# 18-GSM_GPRS_SIM808.net
KiCad netlist of a schematic drawn in Altium Designer
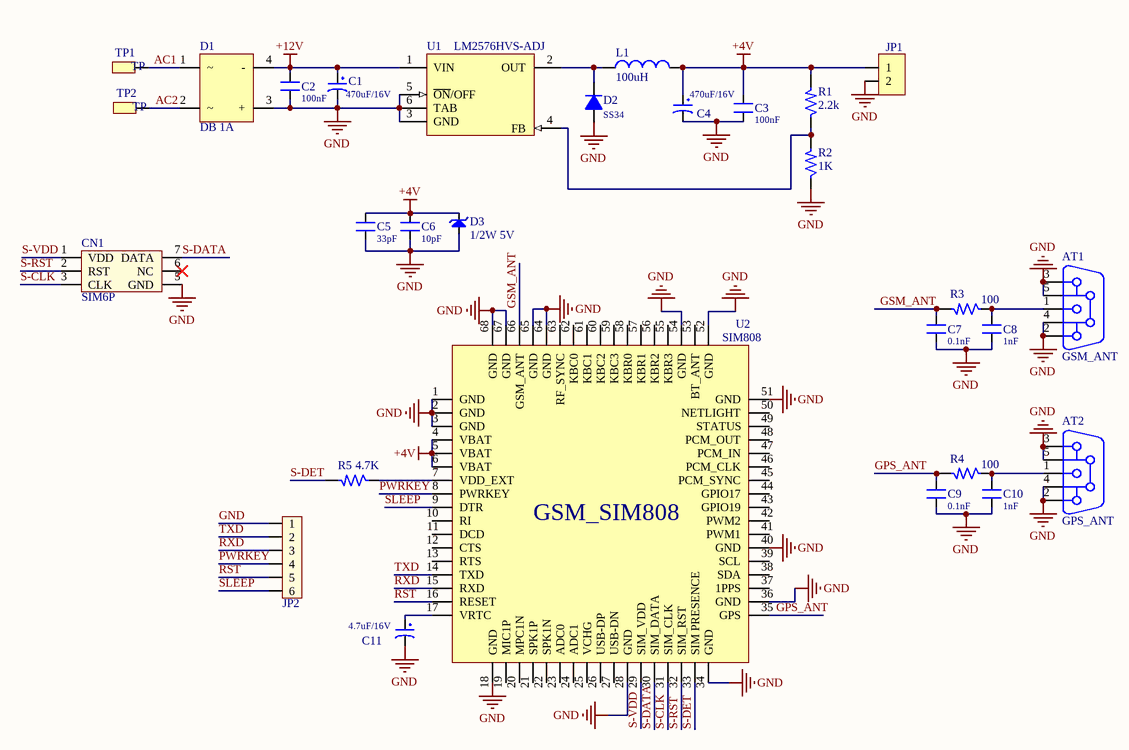
[diagram p0: 18-GSM_GPRS (SIM808).SchDoc]

(export (version "E")
  (design (tool "Eeschema 10.0.6"))
  (components
    (comp (ref "AT1")
      (value "GSM_ANT")
      (footprint "SMA-RA")
      (description "CONNECTOR ANTEN")
      (fields
        (field (name "PARTNO") "210111003")
        (field (name "MANUFACTURER") "Würth Elektronik eiSos GmbH")
        (field (name "CREATED BY") "Christin Zierenner")
      )
      (libsource (lib "LIBRARY") (part "CON Ant"))
    )
    (comp (ref "AT2")
      (value "GPS_ANT")
      (footprint "SMA-RA")
      (description "CONNECTOR ANTEN")
      (fields
        (field (name "PARTNO") "210111003")
        (field (name "MANUFACTURER") "Würth Elektronik eiSos GmbH")
        (field (name "CREATED BY") "Christin Zierenner")
      )
      (libsource (lib "LIBRARY") (part "CON Ant"))
    )
    (comp (ref "C1")
      (value "470uF/16V")
      (footprint "C-TANT-7343")
      (libsource (lib "MrQuan") (part "Capacitor"))
    )
    (comp (ref "C2") (value "100nF") (footprint "CER-0805") (libsource (lib "MrQuan") (part "Ceramic")))
    (comp (ref "C3") (value "100nF") (footprint "CER-0805") (libsource (lib "MrQuan") (part "Ceramic")))
    (comp (ref "C4")
      (value "470uF/16V")
      (footprint "C-TANT-7343")
      (libsource (lib "MrQuan") (part "Capacitor"))
    )
    (comp (ref "C5") (value "33pF") (footprint "CER-0805") (libsource (lib "MrQuan") (part "Ceramic")))
    (comp (ref "C6") (value "10pF") (footprint "CER-0805") (libsource (lib "MrQuan") (part "Ceramic")))
    (comp (ref "C7") (value "0.1nF") (footprint "CER-0805") (libsource (lib "MrQuan") (part "Ceramic")))
    (comp (ref "C8") (value "1nF") (footprint "CER-0805") (libsource (lib "MrQuan") (part "Ceramic")))
    (comp (ref "C9") (value "0.1nF") (footprint "CER-0805") (libsource (lib "MrQuan") (part "Ceramic")))
    (comp (ref "C10") (value "1nF") (footprint "CER-0805") (libsource (lib "MrQuan") (part "Ceramic")))
    (comp (ref "C11")
      (value "4.7uF/16V")
      (footprint "C-TANT-7343")
      (libsource (lib "MrQuan") (part "Capacitor"))
    )
    (comp (ref "CN1")
      (value "SIM6P")
      (footprint "SK-SIM-C707A")
      (libsource (lib "doAnTotNghiep2017Lib") (part "SIM6P"))
    )
    (comp (ref "D1")
      (value "DB 1A")
      (footprint "D-DB-1A-SMD")
      (libsource (lib "doAnTotNghiep2017Lib") (part "DB"))
    )
    (comp (ref "D2") (value "SS34") (footprint "DO-214AC") (libsource (lib "MrQuan") (part "Diode")))
    (comp (ref "D3")
      (value "1/2W 5V")
      (footprint "DIO-SMD-106")
      (description "Zenner")
      (libsource (lib "LIBRARY") (part "DIODE Zener"))
    )
    (comp (ref "JP1")
      (value "JP2")
      (footprint "JP2-C1T")
      (description "WR-PHD 2.54 mm Angled Socket Header")
      (fields
        (field (name "MANUFACTURER") "Würth Elektronik eiSos GmbH")
        (field (name "PARTNO") "613002143121")
        (field (name "CREATED BY") "Karrer Zheng")
      )
      (libsource (lib "LIBRARY") (part "JP2"))
    )
    (comp (ref "JP2") (value "JP6 PIN") (footprint "JP6") (libsource (lib "syhaunguyen") (part "JP6")))
    (comp (ref "L1")
      (value "100uH")
      (footprint "SMD-L-X10-Y10-Z4")
      (description "Inductor")
      (fields (field (name "PUBLISHER") "Altium Limited"))
      (libsource (lib "VNSKILLS2014-ASM") (part "Inductor"))
    )
    (comp (ref "R1") (value "2.2k") (footprint "RES-0805") (libsource (lib "MrQuan") (part "Res1/4W")))
    (comp (ref "R2") (value "1K") (footprint "RES-0805") (libsource (lib "MrQuan") (part "Res1/4W")))
    (comp (ref "R3") (value "100") (footprint "RES-0805") (libsource (lib "MrQuan") (part "Res1/4W")))
    (comp (ref "R4") (value "100") (footprint "RES-0805") (libsource (lib "MrQuan") (part "Res1/4W")))
    (comp (ref "R5") (value "4.7K") (footprint "RES-0805") (libsource (lib "MrQuan") (part "Res1/4W")))
    (comp (ref "TP1")
      (value "1")
      (footprint "TP")
      (description "CONNECT 1")
      (libsource (lib "PART") (part "TP"))
    )
    (comp (ref "TP2")
      (value "1")
      (footprint "TP")
      (description "CONNECT 1")
      (libsource (lib "PART") (part "TP"))
    )
    (comp (ref "U1")
      (value "LM2576HVS-ADJ")
      (footprint "LM2576")
      (description "SIMPLE SWITCHER; 3A Step-Down Voltage Regulator")
      (fields
        (field (name "PARTNUMBER") "LM2576HVS-5.0")
        (field (name "MANUFACTURER") "National Semiconductor")
        (field (name "PUBLISHER") "Altium Limited")
      )
      (libsource (lib "VNSKILLS2014-ASM") (part "LM2576HVS-5.0"))
    )
    (comp (ref "U2") (value "SIM808") (footprint "GSM-SIM808") (libsource (lib "MrQuan") (part "GSM-Sim808")))
  )
  (nets
    (net (code "1") (name "+4V") (class "Default")
      (node (ref "C3") (pin "2") (pinfunction "2_2") (pintype "passive"))
      (node (ref "C4") (pin "1") (pinfunction "1_1") (pintype "passive"))
      (node (ref "C5") (pin "2") (pinfunction "2_2") (pintype "passive"))
      (node (ref "C6") (pin "2") (pinfunction "2_2") (pintype "passive"))
      (node (ref "D3") (pin "2") (pinfunction "K_2") (pintype "passive"))
      (node (ref "JP1") (pin "1") (pinfunction "1_1") (pintype "passive"))
      (node (ref "L1") (pin "2") (pinfunction "2_2") (pintype "passive"))
      (node (ref "R1") (pin "2") (pinfunction "2_2") (pintype "passive"))
      (node (ref "U2") (pin "4") (pinfunction "VBAT_4") (pintype "passive"))
      (node (ref "U2") (pin "5") (pinfunction "VBAT_5") (pintype "passive"))
      (node (ref "U2") (pin "6") (pinfunction "VBAT_6") (pintype "passive"))
    )
    (net (code "2") (name "+12V") (class "Default")
      (node (ref "C1") (pin "1") (pinfunction "1_1") (pintype "passive"))
      (node (ref "C2") (pin "2") (pinfunction "2_2") (pintype "passive"))
      (node (ref "D1") (pin "4") (pinfunction "-_4") (pintype "passive"))
      (node (ref "U1") (pin "1") (pinfunction "VIN_1") (pintype "power_in"))
    )
    (net (code "3") (name "/AC1") (class "Default")
      (node (ref "D1") (pin "1") (pinfunction "~_1") (pintype "passive"))
      (node (ref "TP1") (pin "TP1") (pinfunction "0_TP1") (pintype "passive"))
    )
    (net (code "4") (name "/AC2") (class "Default")
      (node (ref "D1") (pin "2") (pinfunction "~_2") (pintype "passive"))
      (node (ref "TP2") (pin "TP1") (pinfunction "0_TP1") (pintype "passive"))
    )
    (net (code "5") (name "/GPS_ANT") (class "Default")
      (node (ref "C9") (pin "2") (pinfunction "2_2") (pintype "passive"))
      (node (ref "R4") (pin "2") (pinfunction "2_2") (pintype "passive"))
      (node (ref "U2") (pin "35") (pinfunction "GPS_35") (pintype "passive"))
    )
    (net (code "6") (name "/GSM_ANT") (class "Default")
      (node (ref "C7") (pin "2") (pinfunction "2_2") (pintype "passive"))
      (node (ref "R3") (pin "2") (pinfunction "2_2") (pintype "passive"))
      (node (ref "U2") (pin "66") (pinfunction "GSM_ANT_66") (pintype "passive"))
    )
    (net (code "7") (name "/PWRKEY") (class "Default")
      (node (ref "JP2") (pin "4") (pinfunction "4_4") (pintype "passive"))
      (node (ref "U2") (pin "8") (pinfunction "PWRKEY_8") (pintype "passive"))
    )
    (net (code "8") (name "/RST") (class "Default")
      (node (ref "JP2") (pin "5") (pinfunction "5_5") (pintype "passive"))
      (node (ref "U2") (pin "16") (pinfunction "RESET_16") (pintype "passive"))
    )
    (net (code "9") (name "/RXD") (class "Default")
      (node (ref "JP2") (pin "3") (pinfunction "3_3") (pintype "passive"))
      (node (ref "U2") (pin "15") (pinfunction "RXD_15") (pintype "passive"))
    )
    (net (code "10") (name "/S-CLK") (class "Default")
      (node (ref "CN1") (pin "3") (pinfunction "CLK_3") (pintype "passive"))
      (node (ref "U2") (pin "31") (pinfunction "SIM_CLK_31") (pintype "passive"))
    )
    (net (code "11") (name "/S-DATA") (class "Default")
      (node (ref "CN1") (pin "7") (pinfunction "DATA_7") (pintype "passive"))
      (node (ref "U2") (pin "30") (pinfunction "SIM_DATA_30") (pintype "passive"))
    )
    (net (code "12") (name "/S-DET") (class "Default")
      (node (ref "R5") (pin "2") (pinfunction "2_2") (pintype "passive"))
      (node (ref "U2") (pin "33") (pinfunction "SIM_PRESENCE_33") (pintype "passive"))
    )
    (net (code "13") (name "/S-RST") (class "Default")
      (node (ref "CN1") (pin "2") (pinfunction "RST_2") (pintype "passive"))
      (node (ref "U2") (pin "32") (pinfunction "SIM_RST_32") (pintype "passive"))
    )
    (net (code "14") (name "/S-VDD") (class "Default")
      (node (ref "CN1") (pin "1") (pinfunction "VDD_1") (pintype "passive"))
      (node (ref "U2") (pin "29") (pinfunction "SIM_VDD_29") (pintype "passive"))
    )
    (net (code "15") (name "/SLEEP") (class "Default")
      (node (ref "JP2") (pin "6") (pinfunction "6_6") (pintype "passive"))
      (node (ref "U2") (pin "9") (pinfunction "DTR_9") (pintype "passive"))
    )
    (net (code "16") (name "/TXD") (class "Default")
      (node (ref "JP2") (pin "2") (pinfunction "2_2") (pintype "passive"))
      (node (ref "U2") (pin "14") (pinfunction "TXD_14") (pintype "passive"))
    )
    (net (code "17") (name "GND") (class "Default")
      (node (ref "AT1") (pin "2") (pinfunction "2_2") (pintype "passive"))
      (node (ref "AT1") (pin "3") (pinfunction "3_3") (pintype "passive"))
      (node (ref "AT1") (pin "4") (pinfunction "4_4") (pintype "passive"))
      (node (ref "AT1") (pin "5") (pinfunction "5_5") (pintype "passive"))
      (node (ref "AT2") (pin "2") (pinfunction "2_2") (pintype "passive"))
      (node (ref "AT2") (pin "3") (pinfunction "3_3") (pintype "passive"))
      (node (ref "AT2") (pin "4") (pinfunction "4_4") (pintype "passive"))
      (node (ref "AT2") (pin "5") (pinfunction "5_5") (pintype "passive"))
      (node (ref "C1") (pin "2") (pinfunction "2_2") (pintype "passive"))
      (node (ref "C10") (pin "1") (pinfunction "1_1") (pintype "passive"))
      (node (ref "C11") (pin "2") (pinfunction "2_2") (pintype "passive"))
      (node (ref "C2") (pin "1") (pinfunction "1_1") (pintype "passive"))
      (node (ref "C3") (pin "1") (pinfunction "1_1") (pintype "passive"))
      (node (ref "C4") (pin "2") (pinfunction "2_2") (pintype "passive"))
      (node (ref "C5") (pin "1") (pinfunction "1_1") (pintype "passive"))
      (node (ref "C6") (pin "1") (pinfunction "1_1") (pintype "passive"))
      (node (ref "C7") (pin "1") (pinfunction "1_1") (pintype "passive"))
      (node (ref "C8") (pin "1") (pinfunction "1_1") (pintype "passive"))
      (node (ref "C9") (pin "1") (pinfunction "1_1") (pintype "passive"))
      (node (ref "CN1") (pin "5") (pinfunction "GND_5") (pintype "passive"))
      (node (ref "D1") (pin "3") (pinfunction "+_3") (pintype "passive"))
      (node (ref "D2") (pin "1") (pinfunction "A_1") (pintype "passive"))
      (node (ref "D3") (pin "1") (pinfunction "A_1") (pintype "passive"))
      (node (ref "JP1") (pin "2") (pinfunction "2_2") (pintype "passive"))
      (node (ref "JP2") (pin "1") (pinfunction "1_1") (pintype "passive"))
      (node (ref "R2") (pin "1") (pinfunction "1_1") (pintype "passive"))
      (node (ref "U1") (pin "3") (pinfunction "GND_3") (pintype "power_in"))
      (node (ref "U1") (pin "5") (pinfunction "~{ON}/OFF_5") (pintype "input"))
      (node (ref "U1") (pin "6") (pinfunction "TAB_6") (pintype "power_in"))
      (node (ref "U2") (pin "1") (pinfunction "GND_1") (pintype "passive"))
      (node (ref "U2") (pin "18") (pinfunction "GND_18") (pintype "passive"))
      (node (ref "U2") (pin "2") (pinfunction "GND_2") (pintype "passive"))
      (node (ref "U2") (pin "28") (pinfunction "GND_28") (pintype "passive"))
      (node (ref "U2") (pin "3") (pinfunction "GND_3") (pintype "passive"))
      (node (ref "U2") (pin "34") (pinfunction "GND_34") (pintype "passive"))
      (node (ref "U2") (pin "36") (pinfunction "GND_36") (pintype "passive"))
      (node (ref "U2") (pin "40") (pinfunction "GND_40") (pintype "passive"))
      (node (ref "U2") (pin "51") (pinfunction "GND_51") (pintype "passive"))
      (node (ref "U2") (pin "52") (pinfunction "GND_52") (pintype "passive"))
      (node (ref "U2") (pin "54") (pinfunction "GND_54") (pintype "passive"))
      (node (ref "U2") (pin "64") (pinfunction "GND_64") (pintype "passive"))
      (node (ref "U2") (pin "65") (pinfunction "GND_65") (pintype "passive"))
      (node (ref "U2") (pin "67") (pinfunction "GND_67") (pintype "passive"))
      (node (ref "U2") (pin "68") (pinfunction "GND_68") (pintype "passive"))
    )
    (net (code "18") (name "Net-(AT1-Pad1)") (class "Default")
      (node (ref "AT1") (pin "1") (pinfunction "1_1") (pintype "passive"))
      (node (ref "C8") (pin "2") (pinfunction "2_2") (pintype "passive"))
      (node (ref "R3") (pin "1") (pinfunction "1_1") (pintype "passive"))
    )
    (net (code "19") (name "Net-(AT2-Pad1)") (class "Default")
      (node (ref "AT2") (pin "1") (pinfunction "1_1") (pintype "passive"))
      (node (ref "C10") (pin "2") (pinfunction "2_2") (pintype "passive"))
      (node (ref "R4") (pin "1") (pinfunction "1_1") (pintype "passive"))
    )
    (net (code "20") (name "Net-(D2-K)") (class "Default")
      (node (ref "D2") (pin "2") (pinfunction "K_2") (pintype "passive"))
      (node (ref "L1") (pin "1") (pinfunction "1_1") (pintype "passive"))
      (node (ref "U1") (pin "2") (pinfunction "OUT_2") (pintype "power_in"))
    )
    (net (code "21") (name "Net-(U1-FB)") (class "Default")
      (node (ref "R1") (pin "1") (pinfunction "1_1") (pintype "passive"))
      (node (ref "R2") (pin "2") (pinfunction "2_2") (pintype "passive"))
      (node (ref "U1") (pin "4") (pinfunction "FB_4") (pintype "input"))
    )
    (net (code "22") (name "Net-(U2-VDD_EXT)") (class "Default")
      (node (ref "R5") (pin "1") (pinfunction "1_1") (pintype "passive"))
      (node (ref "U2") (pin "7") (pinfunction "VDD_EXT_7") (pintype "passive"))
    )
    (net (code "23") (name "Net-(U2-VRTC)") (class "Default")
      (node (ref "C11") (pin "1") (pinfunction "1_1") (pintype "passive"))
      (node (ref "U2") (pin "17") (pinfunction "VRTC_17") (pintype "passive"))
    )
    (net (code "24") (name "unconnected-(CN1-NC-Pad6)") (class "Default")
      (node (ref "CN1") (pin "6") (pinfunction "NC_6") (pintype "passive+no_connect"))
    )
    (net (code "25") (name "unconnected-(U2-1PPS-Pad37)") (class "Default")
      (node (ref "U2") (pin "37") (pinfunction "1PPS_37") (pintype "passive"))
    )
    (net (code "26") (name "unconnected-(U2-ADC0-Pad23)") (class "Default")
      (node (ref "U2") (pin "23") (pinfunction "ADC0_23") (pintype "passive"))
    )
    (net (code "27") (name "unconnected-(U2-ADC1-Pad24)") (class "Default")
      (node (ref "U2") (pin "24") (pinfunction "ADC1_24") (pintype "passive"))
    )
    (net (code "28") (name "unconnected-(U2-BT_ANT-Pad53)") (class "Default")
      (node (ref "U2") (pin "53") (pinfunction "BT_ANT_53") (pintype "passive"))
    )
    (net (code "29") (name "unconnected-(U2-CTS-Pad12)") (class "Default")
      (node (ref "U2") (pin "12") (pinfunction "CTS_12") (pintype "passive"))
    )
    (net (code "30") (name "unconnected-(U2-DCD-Pad11)") (class "Default")
      (node (ref "U2") (pin "11") (pinfunction "DCD_11") (pintype "passive"))
    )
    (net (code "31") (name "unconnected-(U2-GPIO17-Pad44)") (class "Default")
      (node (ref "U2") (pin "44") (pinfunction "GPIO17_44") (pintype "passive"))
    )
    (net (code "32") (name "unconnected-(U2-GPIO19-Pad43)") (class "Default")
      (node (ref "U2") (pin "43") (pinfunction "GPIO19_43") (pintype "passive"))
    )
    (net (code "33") (name "unconnected-(U2-KBC0-Pad62)") (class "Default")
      (node (ref "U2") (pin "62") (pinfunction "KBC0_62") (pintype "passive"))
    )
    (net (code "34") (name "unconnected-(U2-KBC1-Pad61)") (class "Default")
      (node (ref "U2") (pin "61") (pinfunction "KBC1_61") (pintype "passive"))
    )
    (net (code "35") (name "unconnected-(U2-KBC2-Pad60)") (class "Default")
      (node (ref "U2") (pin "60") (pinfunction "KBC2_60") (pintype "passive"))
    )
    (net (code "36") (name "unconnected-(U2-KBC3-Pad59)") (class "Default")
      (node (ref "U2") (pin "59") (pinfunction "KBC3_59") (pintype "passive"))
    )
    (net (code "37") (name "unconnected-(U2-KBR0-Pad58)") (class "Default")
      (node (ref "U2") (pin "58") (pinfunction "KBR0_58") (pintype "passive"))
    )
    (net (code "38") (name "unconnected-(U2-KBR1-Pad57)") (class "Default")
      (node (ref "U2") (pin "57") (pinfunction "KBR1_57") (pintype "passive"))
    )
    (net (code "39") (name "unconnected-(U2-KBR2-Pad56)") (class "Default")
      (node (ref "U2") (pin "56") (pinfunction "KBR2_56") (pintype "passive"))
    )
    (net (code "40") (name "unconnected-(U2-KBR3-Pad55)") (class "Default")
      (node (ref "U2") (pin "55") (pinfunction "KBR3_55") (pintype "passive"))
    )
    (net (code "41") (name "unconnected-(U2-MIC1P-Pad19)") (class "Default")
      (node (ref "U2") (pin "19") (pinfunction "MIC1P_19") (pintype "passive"))
    )
    (net (code "42") (name "unconnected-(U2-MPC1N-Pad20)") (class "Default")
      (node (ref "U2") (pin "20") (pinfunction "MPC1N_20") (pintype "passive"))
    )
    (net (code "43") (name "unconnected-(U2-NETLIGHT-Pad50)") (class "Default")
      (node (ref "U2") (pin "50") (pinfunction "NETLIGHT_50") (pintype "passive"))
    )
    (net (code "44") (name "unconnected-(U2-PCM_CLK-Pad46)") (class "Default")
      (node (ref "U2") (pin "46") (pinfunction "PCM_CLK_46") (pintype "passive"))
    )
    (net (code "45") (name "unconnected-(U2-PCM_IN-Pad47)") (class "Default")
      (node (ref "U2") (pin "47") (pinfunction "PCM_IN_47") (pintype "passive"))
    )
    (net (code "46") (name "unconnected-(U2-PCM_OUT-Pad48)") (class "Default")
      (node (ref "U2") (pin "48") (pinfunction "PCM_OUT_48") (pintype "passive"))
    )
    (net (code "47") (name "unconnected-(U2-PCM_SYNC-Pad45)") (class "Default")
      (node (ref "U2") (pin "45") (pinfunction "PCM_SYNC_45") (pintype "passive"))
    )
    (net (code "48") (name "unconnected-(U2-PWM1-Pad41)") (class "Default")
      (node (ref "U2") (pin "41") (pinfunction "PWM1_41") (pintype "passive"))
    )
    (net (code "49") (name "unconnected-(U2-PWM2-Pad42)") (class "Default")
      (node (ref "U2") (pin "42") (pinfunction "PWM2_42") (pintype "passive"))
    )
    (net (code "50") (name "unconnected-(U2-RF_SYNC-Pad63)") (class "Default")
      (node (ref "U2") (pin "63") (pinfunction "RF_SYNC_63") (pintype "passive"))
    )
    (net (code "51") (name "unconnected-(U2-RI-Pad10)") (class "Default")
      (node (ref "U2") (pin "10") (pinfunction "RI_10") (pintype "passive"))
    )
    (net (code "52") (name "unconnected-(U2-RTS-Pad13)") (class "Default")
      (node (ref "U2") (pin "13") (pinfunction "RTS_13") (pintype "passive"))
    )
    (net (code "53") (name "unconnected-(U2-SCL-Pad39)") (class "Default")
      (node (ref "U2") (pin "39") (pinfunction "SCL_39") (pintype "passive"))
    )
    (net (code "54") (name "unconnected-(U2-SDA-Pad38)") (class "Default")
      (node (ref "U2") (pin "38") (pinfunction "SDA_38") (pintype "passive"))
    )
    (net (code "55") (name "unconnected-(U2-SPK1N-Pad22)") (class "Default")
      (node (ref "U2") (pin "22") (pinfunction "SPK1N_22") (pintype "passive"))
    )
    (net (code "56") (name "unconnected-(U2-SPK1P-Pad21)") (class "Default")
      (node (ref "U2") (pin "21") (pinfunction "SPK1P_21") (pintype "passive"))
    )
    (net (code "57") (name "unconnected-(U2-STATUS-Pad49)") (class "Default")
      (node (ref "U2") (pin "49") (pinfunction "STATUS_49") (pintype "passive"))
    )
    (net (code "58") (name "unconnected-(U2-USB-DN-Pad27)") (class "Default")
      (node (ref "U2") (pin "27") (pinfunction "USB-DN_27") (pintype "passive"))
    )
    (net (code "59") (name "unconnected-(U2-USB-DP-Pad26)") (class "Default")
      (node (ref "U2") (pin "26") (pinfunction "USB-DP_26") (pintype "passive"))
    )
    (net (code "60") (name "unconnected-(U2-VCHG-Pad25)") (class "Default")
      (node (ref "U2") (pin "25") (pinfunction "VCHG_25") (pintype "passive"))
    )
  )
)
